# MastersProjectTestBed.net
KiCad netlist of a schematic drawn in EAGLE
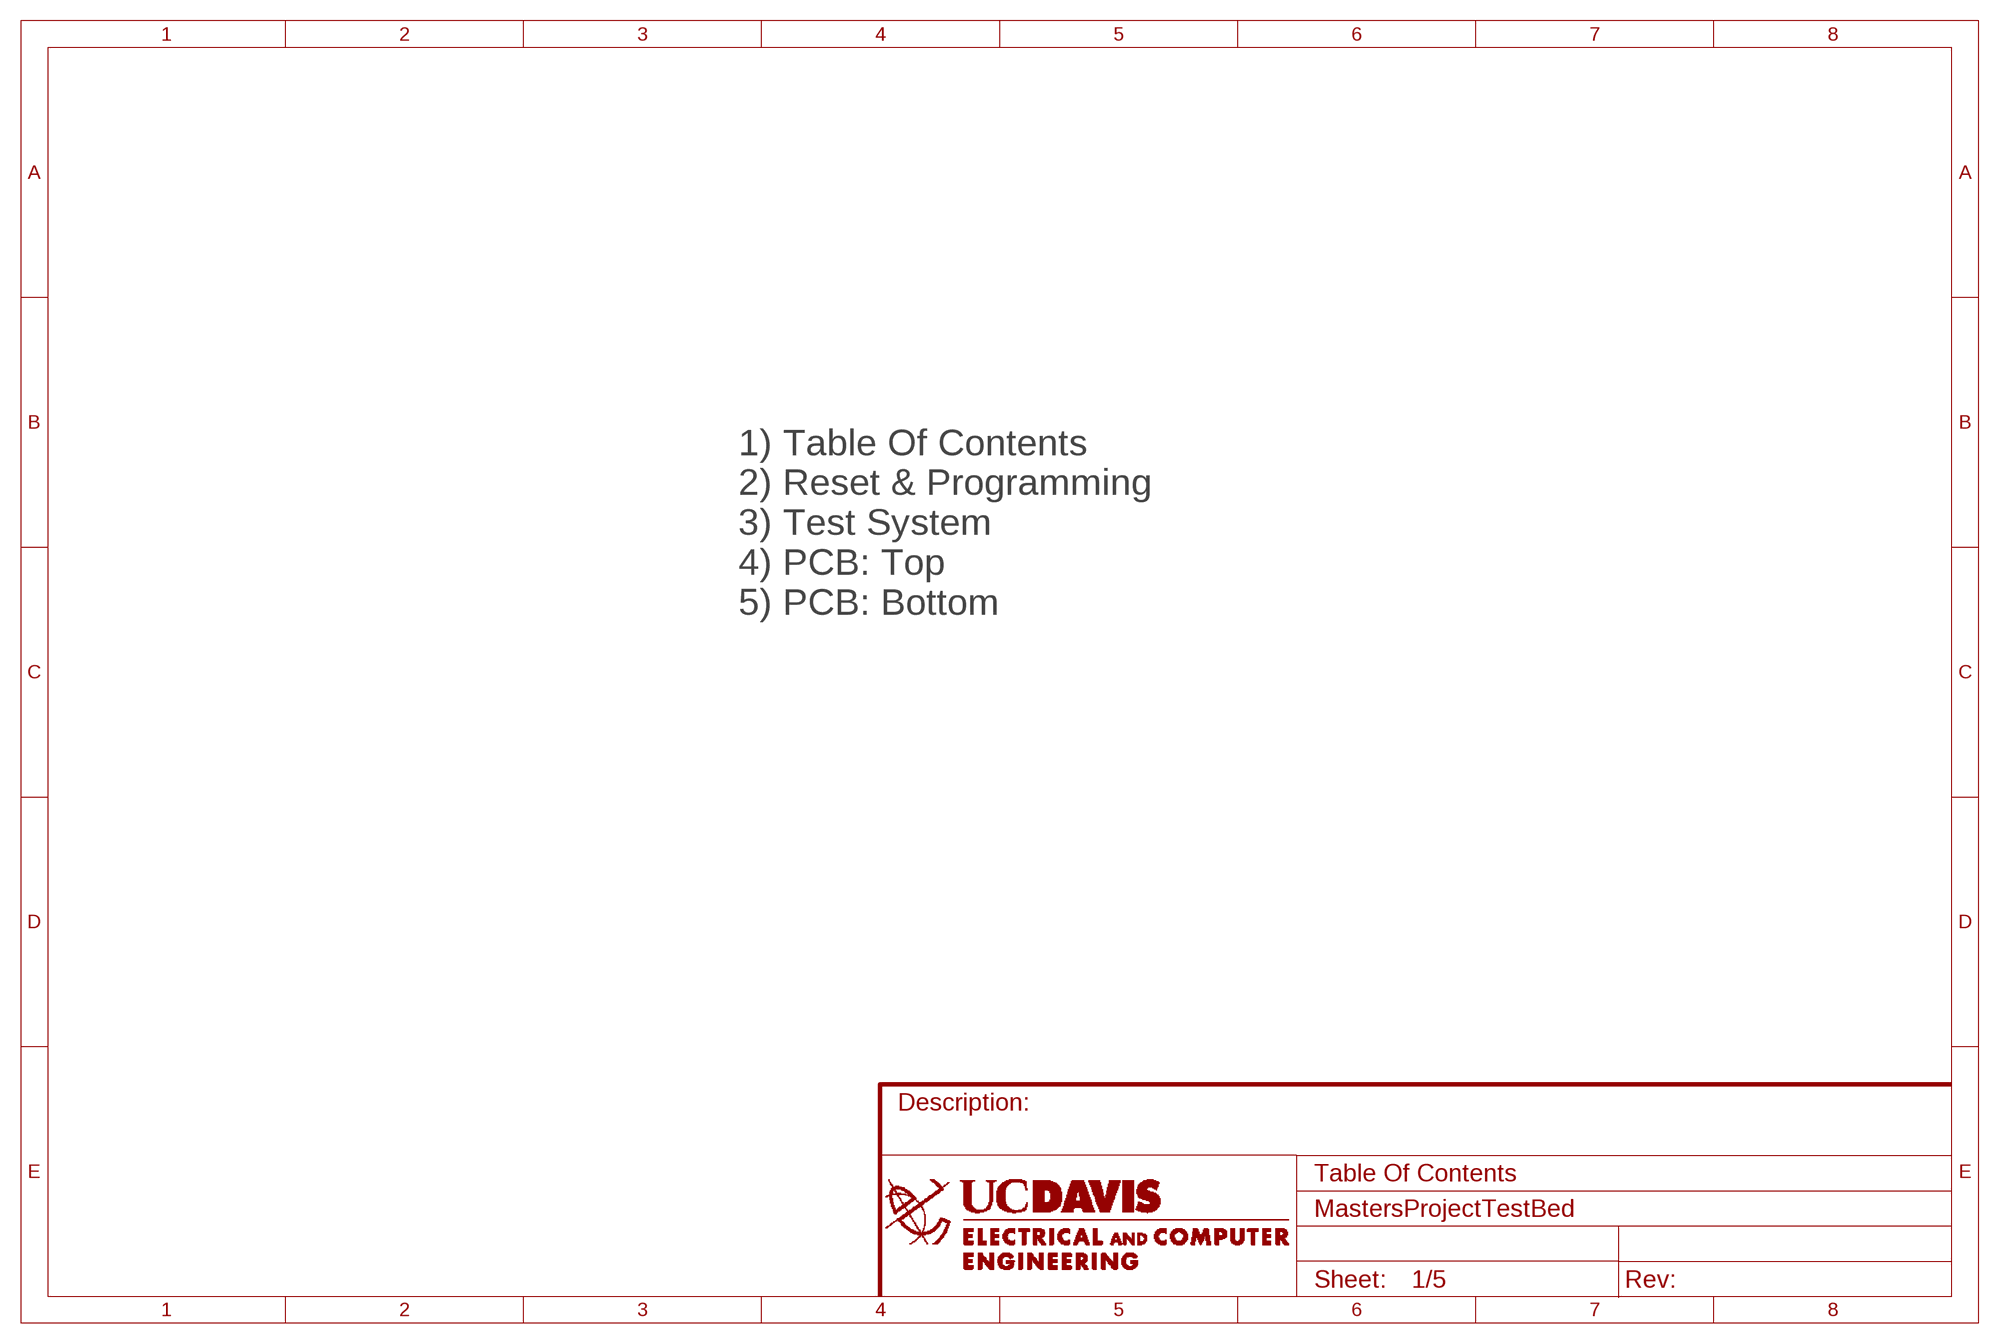
[diagram p0: schematic, sheet 1]
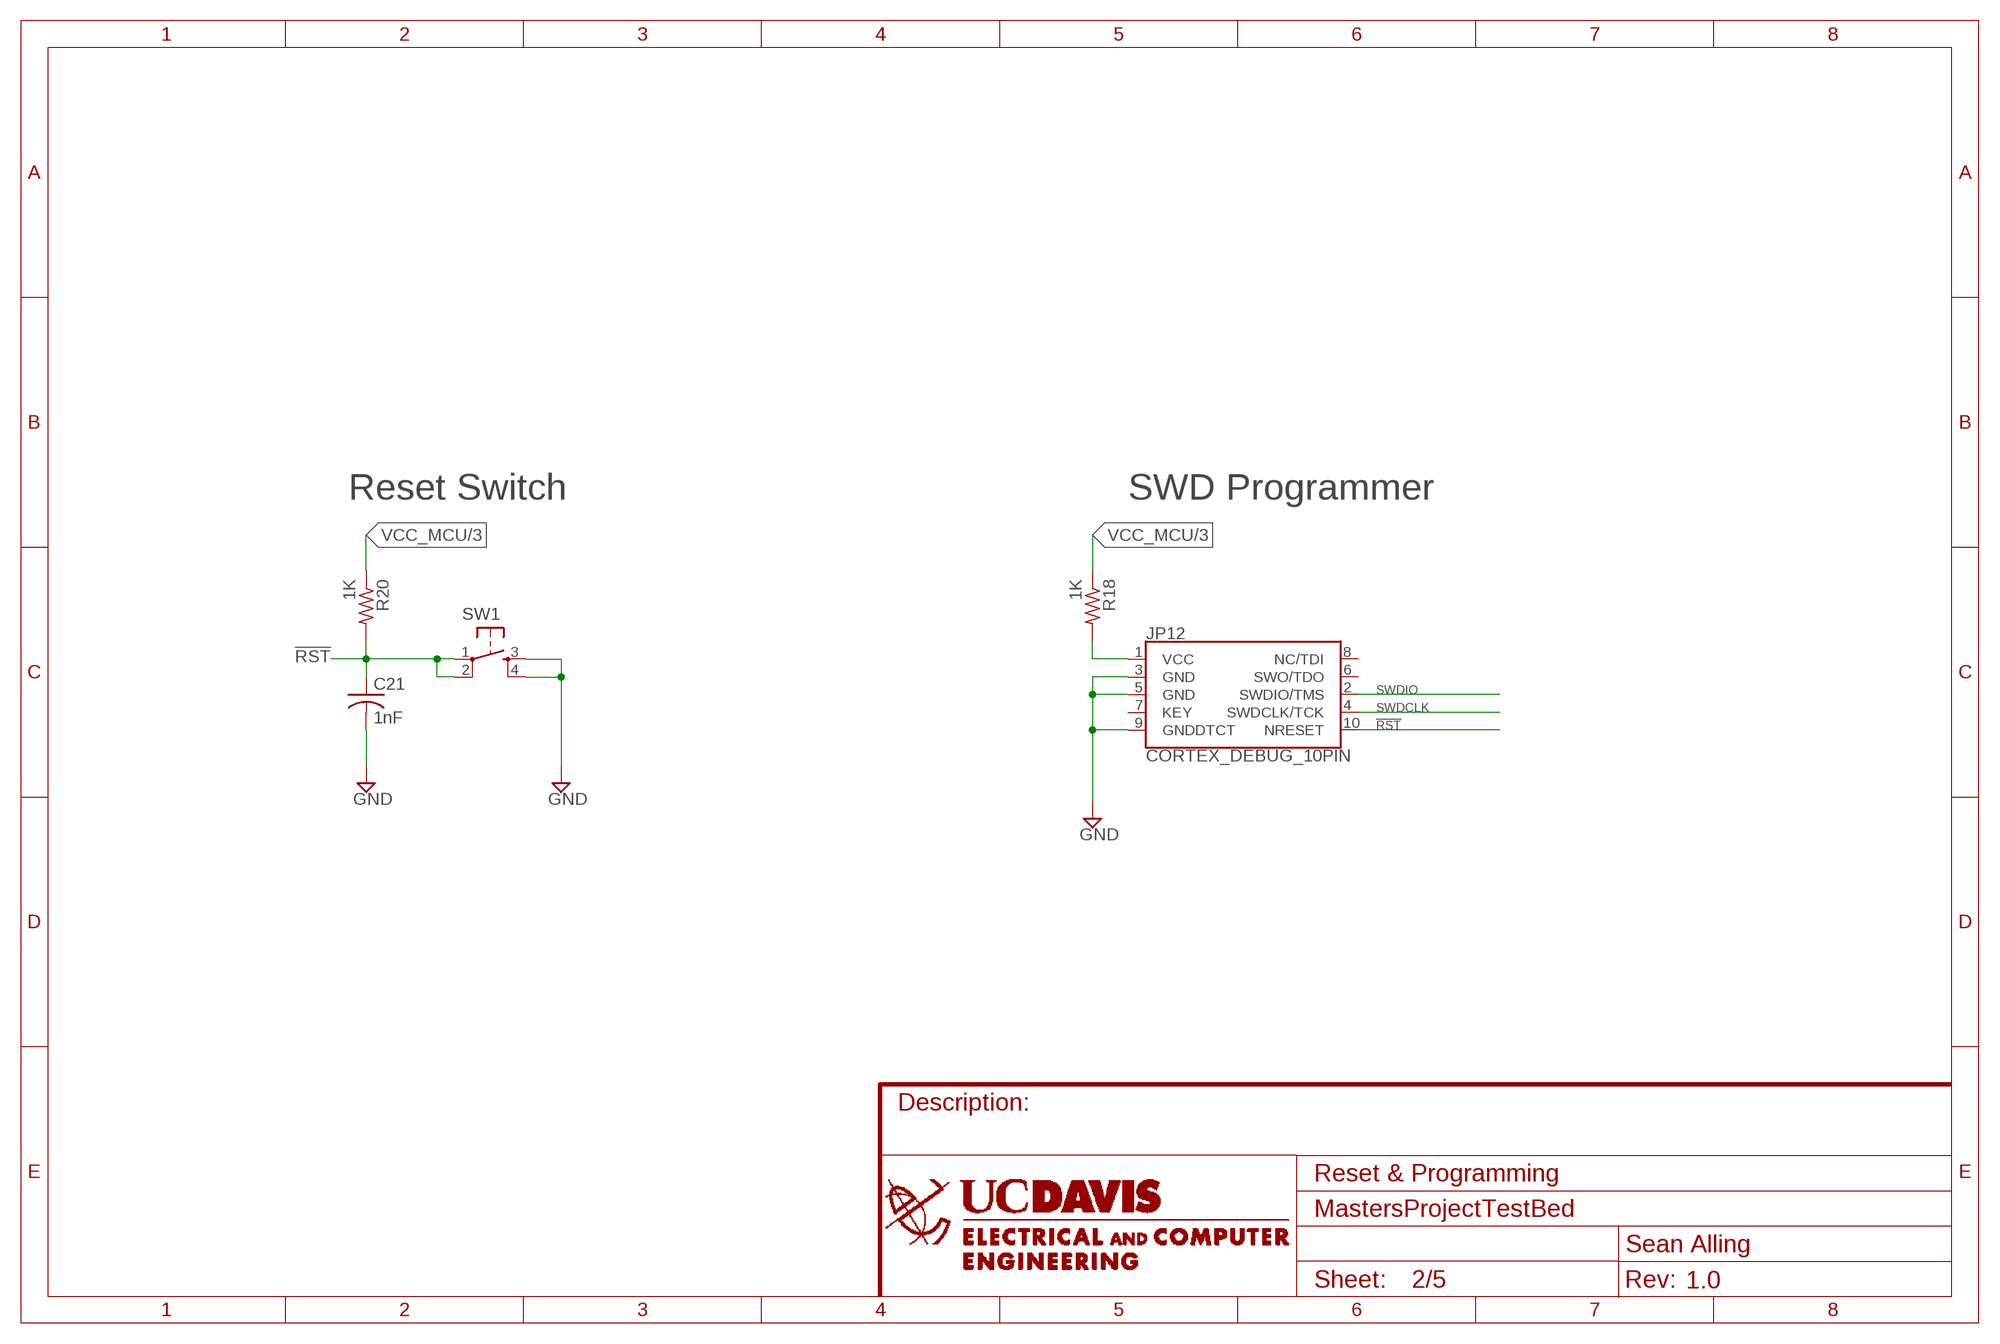
[diagram p1: schematic, sheet 2]
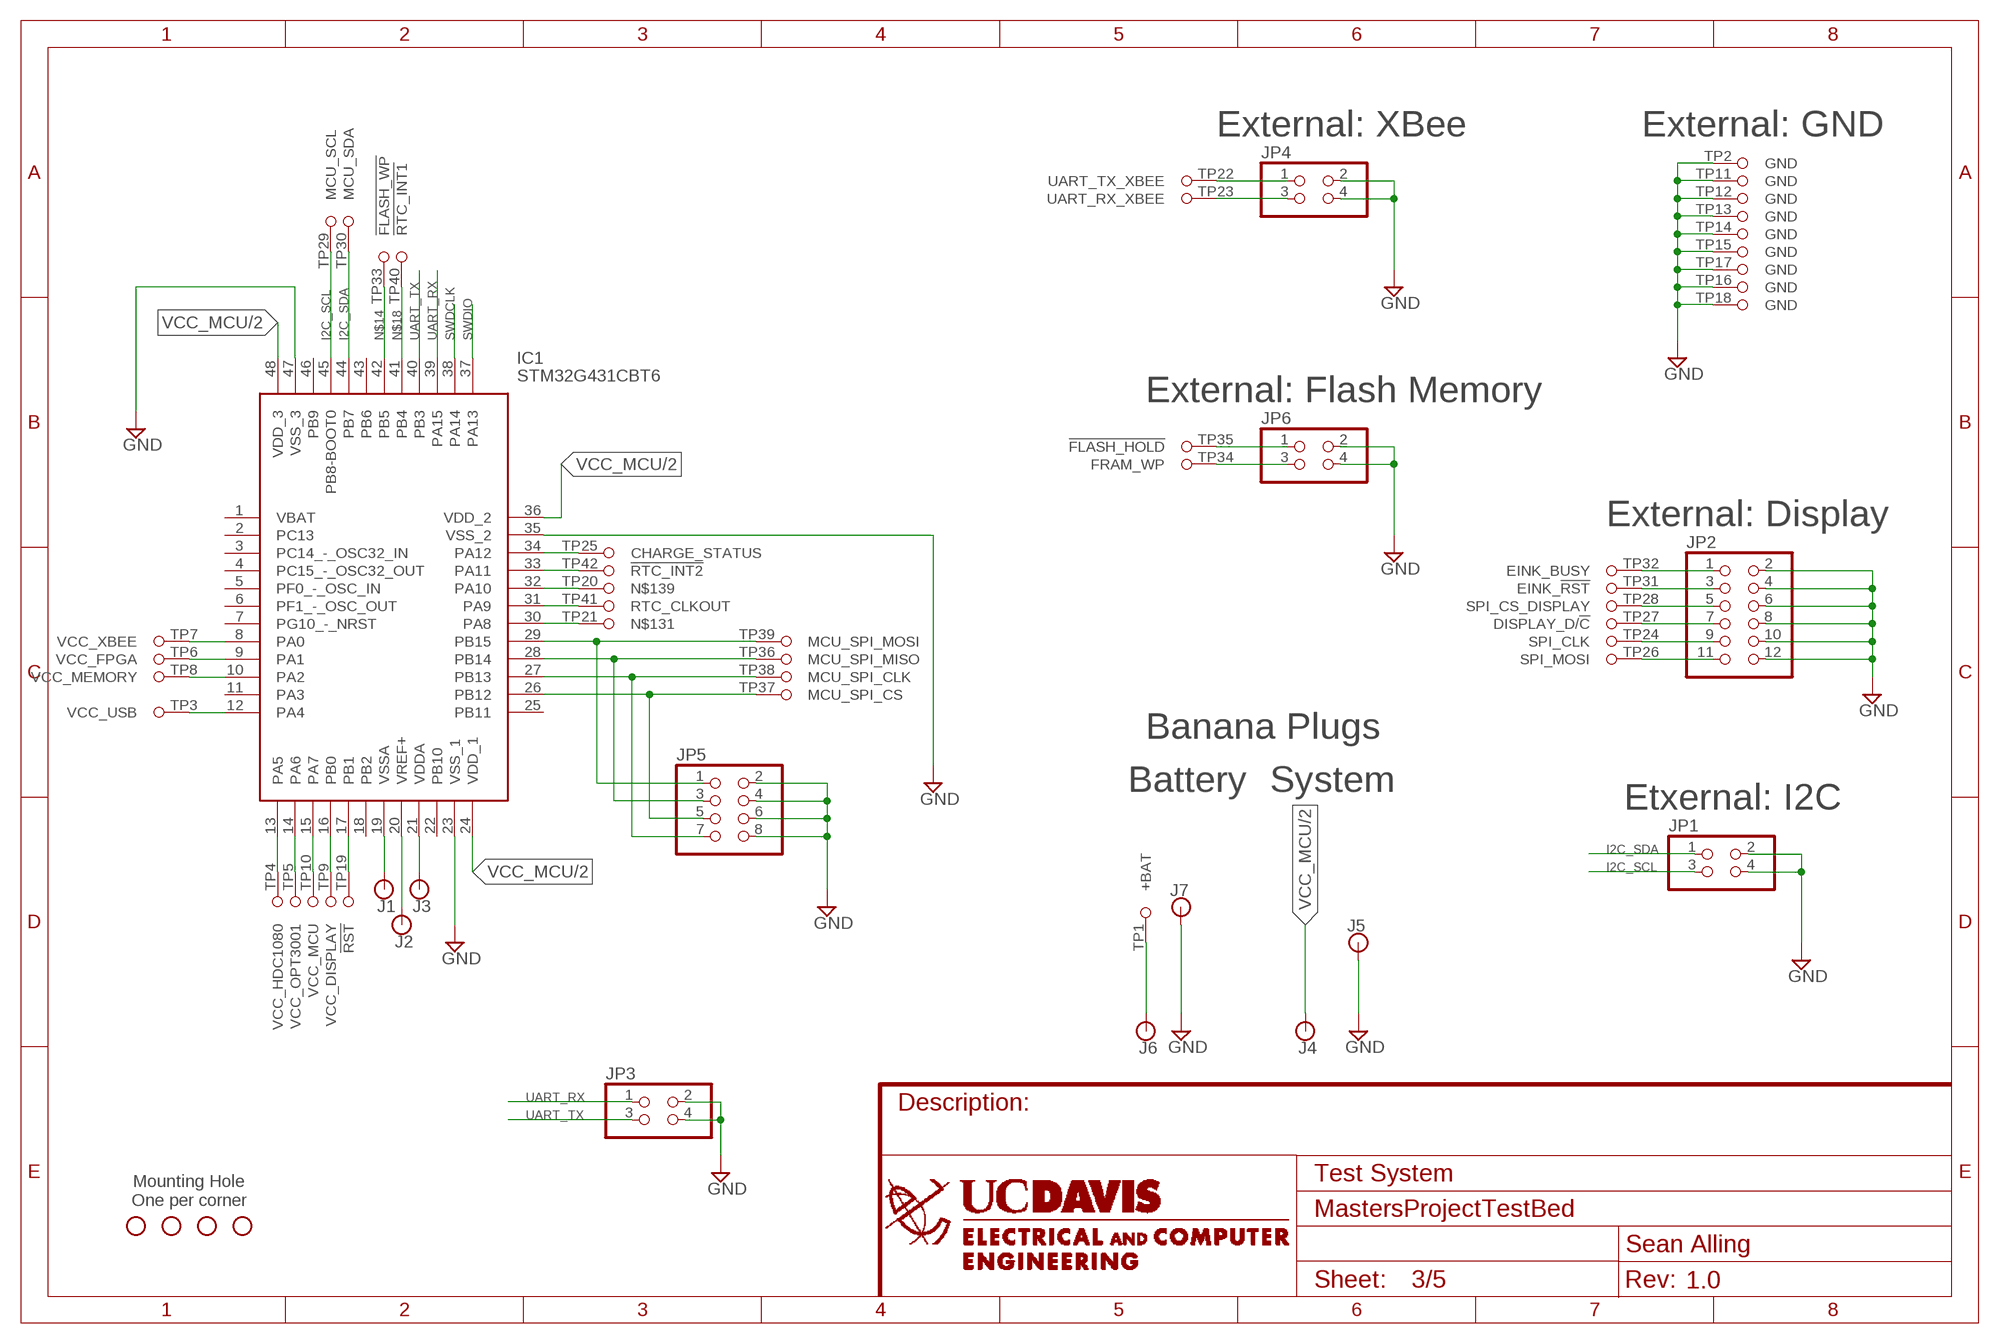
[diagram p2: schematic, sheet 3]
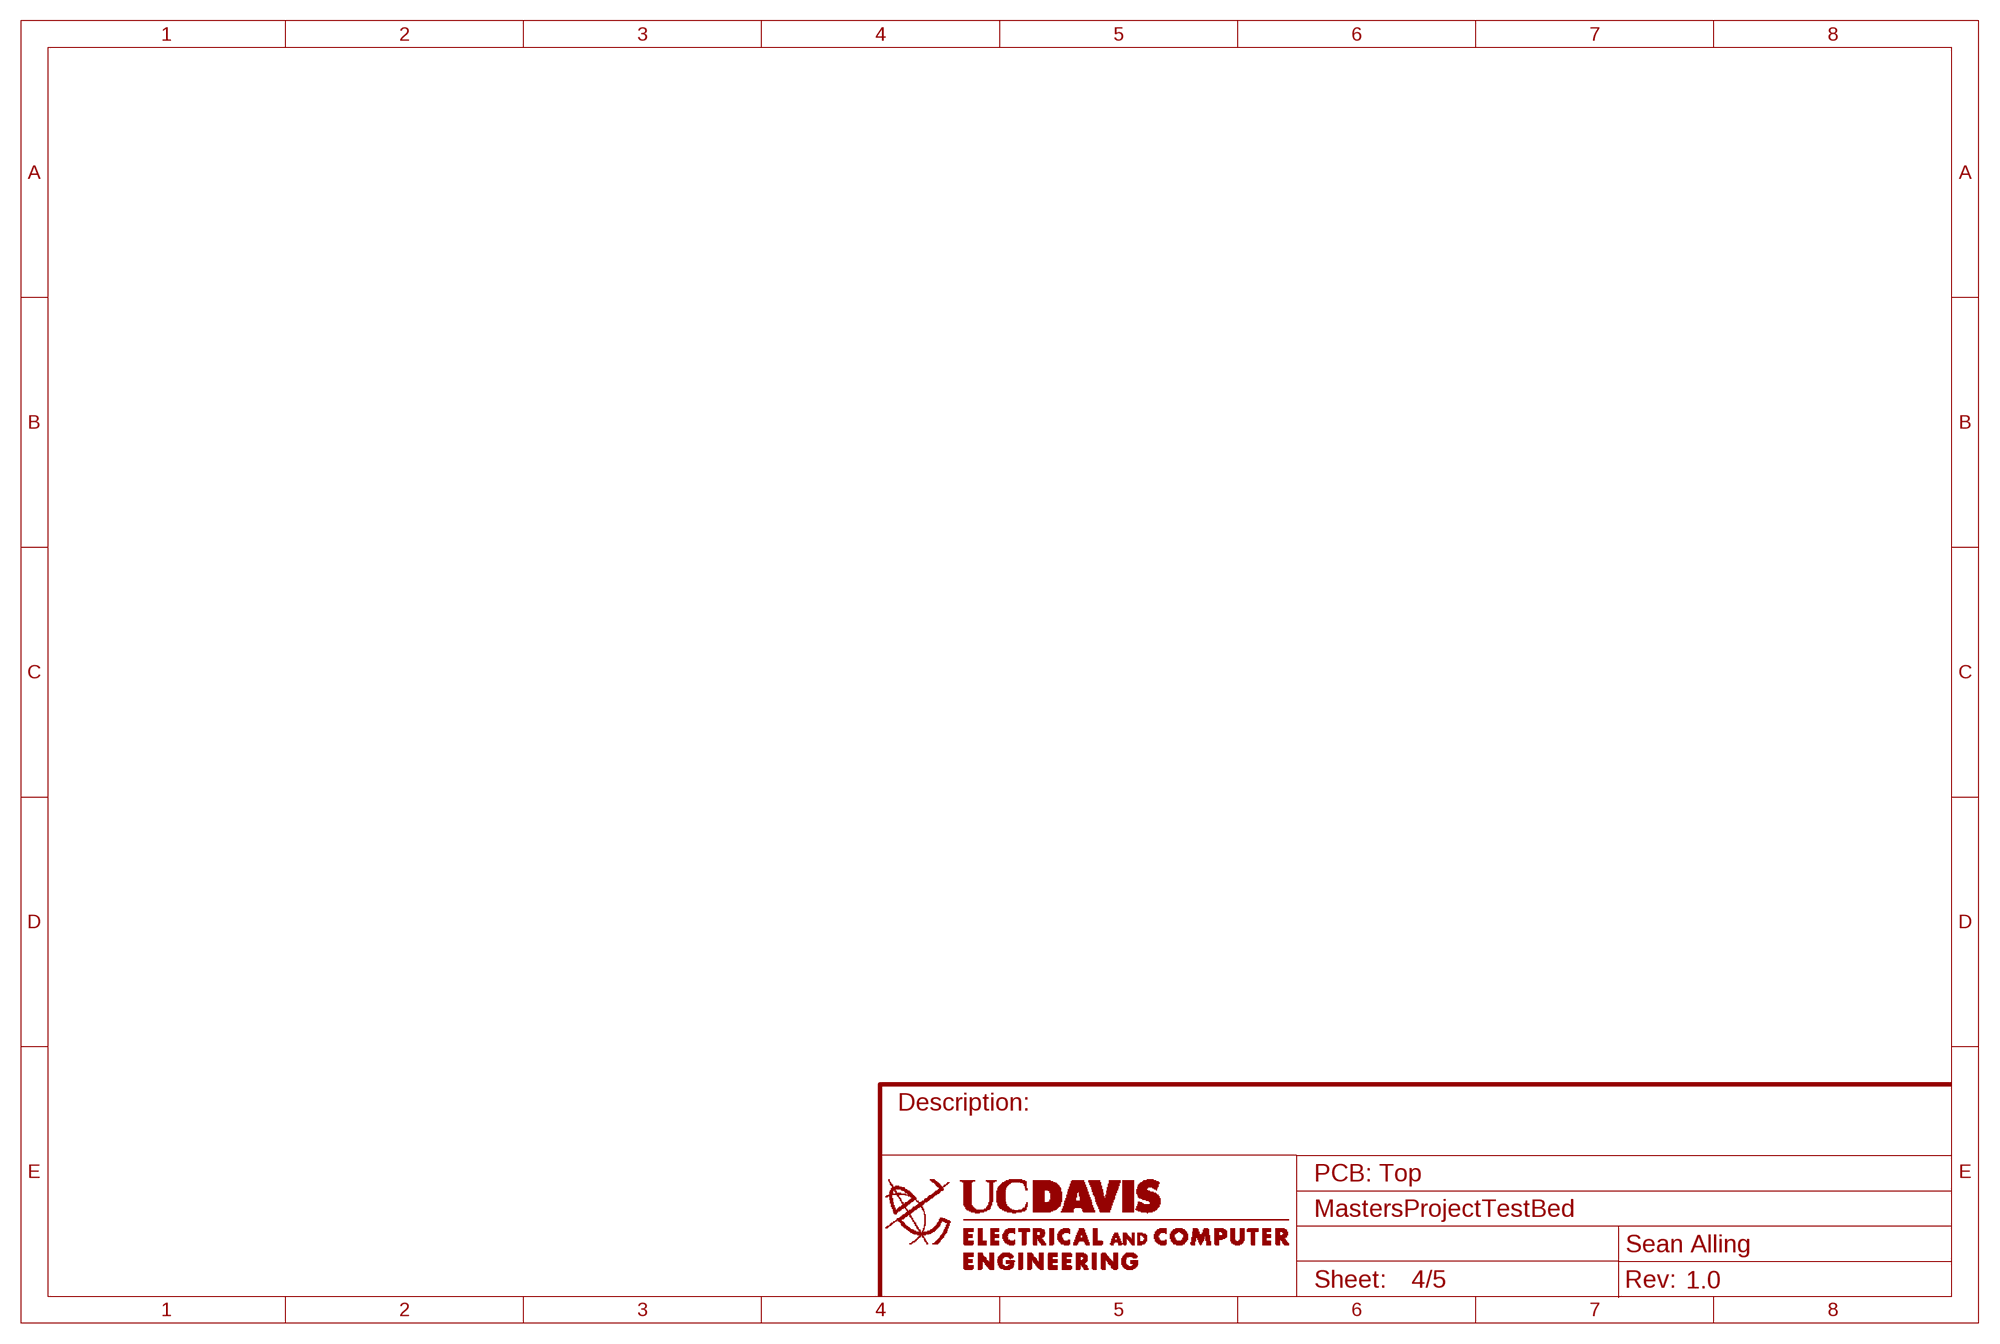
[diagram p3: schematic, sheet 4]
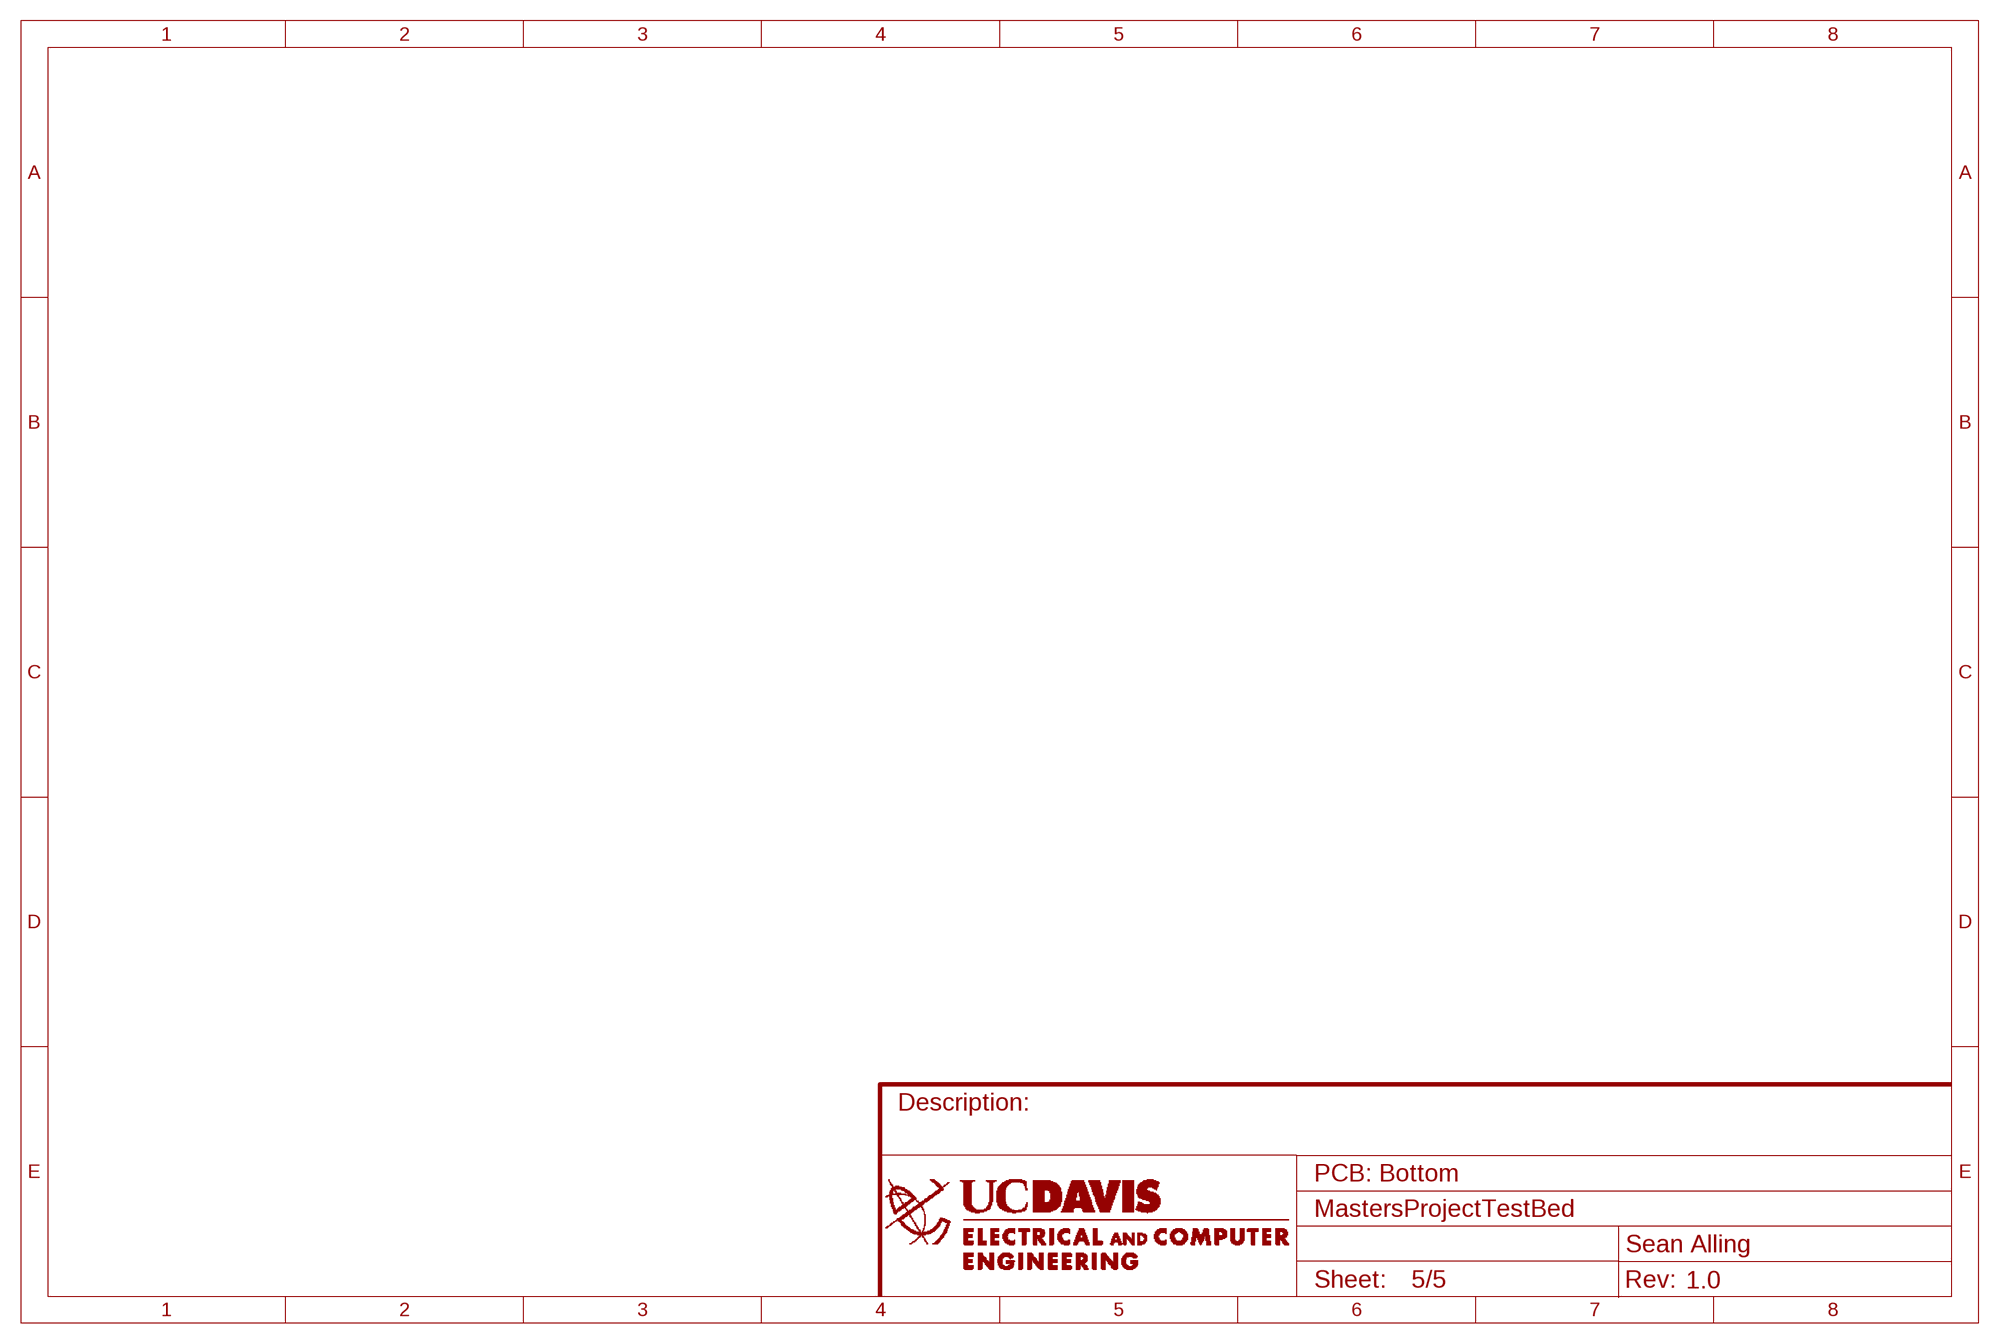
[diagram p4: schematic, sheet 5]

(export (version "E")
  (design (tool "Eeschema 10.0.6"))
  (components
    (comp (ref "H1")
      (value "STAND-OFF")
      (footprint "eagle-import:STAND-OFF")
      (libsource (lib "eagle-import") (part "STAND-OFF"))
    )
    (comp (ref "H2")
      (value "STAND-OFF")
      (footprint "eagle-import:STAND-OFF")
      (libsource (lib "eagle-import") (part "STAND-OFF"))
    )
    (comp (ref "H3")
      (value "STAND-OFF")
      (footprint "eagle-import:STAND-OFF")
      (libsource (lib "eagle-import") (part "STAND-OFF"))
    )
    (comp (ref "H4")
      (value "STAND-OFF")
      (footprint "eagle-import:STAND-OFF")
      (libsource (lib "eagle-import") (part "STAND-OFF"))
    )
    (comp (ref "IC1")
      (value "STM32G431CBT6")
      (footprint "eagle-import:QFP50P900X900X160-48N")
      (fields (field (name "MOUSER_PART_NUMBER") "511-STM32G431CBT6"))
      (libsource (lib "eagle-import") (part "STM32G431CBT6"))
    )
    (comp (ref "J1")
      (value "BANANA_CONN")
      (footprint "eagle-import:BANANA_CONN")
      (libsource (lib "eagle-import") (part "BANANA_CONN"))
    )
    (comp (ref "J2")
      (value "BANANA_CONN")
      (footprint "eagle-import:BANANA_CONN")
      (libsource (lib "eagle-import") (part "BANANA_CONN"))
    )
    (comp (ref "J3")
      (value "BANANA_CONN")
      (footprint "eagle-import:BANANA_CONN")
      (libsource (lib "eagle-import") (part "BANANA_CONN"))
    )
    (comp (ref "J4")
      (value "BANANA_CONN")
      (footprint "eagle-import:BANANA_CONN")
      (libsource (lib "eagle-import") (part "BANANA_CONN"))
    )
    (comp (ref "J5")
      (value "BANANA_CONN")
      (footprint "eagle-import:BANANA_CONN")
      (libsource (lib "eagle-import") (part "BANANA_CONN"))
    )
    (comp (ref "J6")
      (value "BANANA_CONN")
      (footprint "eagle-import:BANANA_CONN")
      (libsource (lib "eagle-import") (part "BANANA_CONN"))
    )
    (comp (ref "J7")
      (value "BANANA_CONN")
      (footprint "eagle-import:BANANA_CONN")
      (libsource (lib "eagle-import") (part "BANANA_CONN"))
    )
    (comp (ref "JP1")
      (value "PINHD-2X2/90")
      (footprint "eagle-import:2X02_90")
      (libsource (lib "eagle-import") (part "PINHD-2X2/90"))
    )
    (comp (ref "JP2")
      (value "PINHD-2X6/90")
      (footprint "eagle-import:2X06_90")
      (libsource (lib "eagle-import") (part "PINHD-2X6/90"))
    )
    (comp (ref "JP3")
      (value "PINHD-2X2/90")
      (footprint "eagle-import:2X02_90")
      (libsource (lib "eagle-import") (part "PINHD-2X2/90"))
    )
    (comp (ref "JP4")
      (value "PINHD-2X2/90")
      (footprint "eagle-import:2X02_90")
      (libsource (lib "eagle-import") (part "PINHD-2X2/90"))
    )
    (comp (ref "JP5")
      (value "PINHD-2X4/90")
      (footprint "eagle-import:2X04_90")
      (libsource (lib "eagle-import") (part "PINHD-2X4/90"))
    )
    (comp (ref "JP6")
      (value "PINHD-2X2/90")
      (footprint "eagle-import:2X02_90")
      (libsource (lib "eagle-import") (part "PINHD-2X2/90"))
    )
    (comp (ref "TP1")
      (value "PCB-POGO")
      (footprint "eagle-import:PCB-POGO")
      (libsource (lib "eagle-import") (part "PCB-POGO"))
    )
    (comp (ref "C21")
      (value "1nF")
      (footprint "eagle-import:C0603")
      (fields (field (name "PARTNO") "08053F102K4T2A"))
      (libsource (lib "eagle-import") (part "C-USC0603"))
    )
    (comp (ref "JP12")
      (value "CORTEX_DEBUG_10PIN")
      (footprint "eagle-import:CORTEX_DEBUG_10PIN")
      (fields (field (name "PARTNO") "3220-10-0100-00"))
      (libsource (lib "eagle-import") (part "CORTEX_DEBUG_10PIN"))
    )
    (comp (ref "R18")
      (value "1K")
      (footprint "eagle-import:R0603")
      (fields (field (name "PARTNO") "RC0805JR-071KL"))
      (libsource (lib "eagle-import") (part "R-US_R0603"))
    )
    (comp (ref "R20")
      (value "1K")
      (footprint "eagle-import:R0603")
      (fields (field (name "PARTNO") "RC0805JR-071KL"))
      (libsource (lib "eagle-import") (part "R-US_R0603"))
    )
    (comp (ref "SW1")
      (value "TACTILE-SWITCH-SMT")
      (footprint "eagle-import:7914G")
      (fields (field (name "PARTNO") "7914G-1-000E"))
      (libsource (lib "eagle-import") (part "TACTILE-SWITCH-SMT"))
    )
  )
  (nets
    (net (code "1") (name "GND") (class "Default")
      (node (ref "C21") (pin "2") (pinfunction "2_2") (pintype "passive"))
      (node (ref "IC1") (pin "23") (pinfunction "VSS_1_23") (pintype "bidirectional"))
      (node (ref "IC1") (pin "35") (pinfunction "VSS_2_35") (pintype "bidirectional"))
      (node (ref "IC1") (pin "47") (pinfunction "VSS_3_47") (pintype "bidirectional"))
      (node (ref "J5") (pin "P$1") (pinfunction "1_P$1") (pintype "passive"))
      (node (ref "J7") (pin "P$1") (pinfunction "1_P$1") (pintype "passive"))
      (node (ref "JP1") (pin "2") (pinfunction "2_2") (pintype "passive"))
      (node (ref "JP1") (pin "4") (pinfunction "4_4") (pintype "passive"))
      (node (ref "JP12") (pin "3") (pinfunction "GND_3") (pintype "bidirectional"))
      (node (ref "JP12") (pin "5") (pinfunction "GND_5") (pintype "bidirectional"))
      (node (ref "JP12") (pin "9") (pinfunction "GNDDTCT_9") (pintype "bidirectional"))
      (node (ref "JP2") (pin "10") (pinfunction "10_10") (pintype "passive"))
      (node (ref "JP2") (pin "12") (pinfunction "12_12") (pintype "passive"))
      (node (ref "JP2") (pin "2") (pinfunction "2_2") (pintype "passive"))
      (node (ref "JP2") (pin "4") (pinfunction "4_4") (pintype "passive"))
      (node (ref "JP2") (pin "6") (pinfunction "6_6") (pintype "passive"))
      (node (ref "JP2") (pin "8") (pinfunction "8_8") (pintype "passive"))
      (node (ref "JP3") (pin "2") (pinfunction "2_2") (pintype "passive"))
      (node (ref "JP3") (pin "4") (pinfunction "4_4") (pintype "passive"))
      (node (ref "JP4") (pin "2") (pinfunction "2_2") (pintype "passive"))
      (node (ref "JP4") (pin "4") (pinfunction "4_4") (pintype "passive"))
      (node (ref "JP5") (pin "2") (pinfunction "2_2") (pintype "passive"))
      (node (ref "JP5") (pin "4") (pinfunction "4_4") (pintype "passive"))
      (node (ref "JP5") (pin "6") (pinfunction "6_6") (pintype "passive"))
      (node (ref "JP5") (pin "8") (pinfunction "8_8") (pintype "passive"))
      (node (ref "JP6") (pin "2") (pinfunction "2_2") (pintype "passive"))
      (node (ref "JP6") (pin "4") (pinfunction "4_4") (pintype "passive"))
      (node (ref "SW1") (pin "3") (pinfunction "3_3") (pintype "passive"))
      (node (ref "SW1") (pin "4") (pinfunction "4_4") (pintype "passive"))
      (node (ref "TP1") (pin "TP11") (pinfunction "GND_TP11") (pintype "bidirectional"))
      (node (ref "TP1") (pin "TP12") (pinfunction "GND_TP12") (pintype "bidirectional"))
      (node (ref "TP1") (pin "TP13") (pinfunction "GND_TP13") (pintype "bidirectional"))
      (node (ref "TP1") (pin "TP14") (pinfunction "GND_TP14") (pintype "bidirectional"))
      (node (ref "TP1") (pin "TP15") (pinfunction "GND_TP15") (pintype "bidirectional"))
      (node (ref "TP1") (pin "TP16") (pinfunction "GND_TP16") (pintype "bidirectional"))
      (node (ref "TP1") (pin "TP17") (pinfunction "GND_TP17") (pintype "bidirectional"))
      (node (ref "TP1") (pin "TP18") (pinfunction "GND_TP18") (pintype "bidirectional"))
      (node (ref "TP1") (pin "TP2") (pinfunction "GND_TP2") (pintype "bidirectional"))
    )
    (net (code "2") (name "I2C_SCL") (class "Default")
      (node (ref "IC1") (pin "45") (pinfunction "PB8-BOOT0_45") (pintype "bidirectional"))
      (node (ref "JP1") (pin "3") (pinfunction "3_3") (pintype "passive"))
      (node (ref "TP1") (pin "TP29") (pinfunction "MCU_SCL_TP29") (pintype "bidirectional"))
    )
    (net (code "3") (name "I2C_SDA") (class "Default")
      (node (ref "IC1") (pin "44") (pinfunction "PB7_44") (pintype "bidirectional"))
      (node (ref "JP1") (pin "1") (pinfunction "1_1") (pintype "passive"))
      (node (ref "TP1") (pin "TP30") (pinfunction "MCU_SDA_TP30") (pintype "bidirectional"))
    )
    (net (code "4") (name "N$14") (class "Default")
      (node (ref "IC1") (pin "42") (pinfunction "PB5_42") (pintype "bidirectional"))
      (node (ref "TP1") (pin "TP33") (pinfunction "~{FLASH_WP}_TP33") (pintype "bidirectional"))
    )
    (net (code "5") (name "N$18") (class "Default")
      (node (ref "IC1") (pin "41") (pinfunction "PB4_41") (pintype "bidirectional"))
      (node (ref "TP1") (pin "TP40") (pinfunction "~{RTC_INT1}_TP40") (pintype "bidirectional"))
    )
    (net (code "6") (name "Net-(IC1-PA0)") (class "Default")
      (node (ref "IC1") (pin "8") (pinfunction "PA0_8") (pintype "bidirectional"))
      (node (ref "TP1") (pin "TP7") (pinfunction "VCC_XBEE_TP7") (pintype "bidirectional"))
    )
    (net (code "7") (name "Net-(IC1-PA1)") (class "Default")
      (node (ref "IC1") (pin "9") (pinfunction "PA1_9") (pintype "bidirectional"))
      (node (ref "TP1") (pin "TP6") (pinfunction "VCC_FPGA_TP6") (pintype "bidirectional"))
    )
    (net (code "8") (name "Net-(IC1-PA2)") (class "Default")
      (node (ref "IC1") (pin "10") (pinfunction "PA2_10") (pintype "bidirectional"))
      (node (ref "TP1") (pin "TP8") (pinfunction "VCC_MEMORY_TP8") (pintype "bidirectional"))
    )
    (net (code "9") (name "Net-(IC1-PA4)") (class "Default")
      (node (ref "IC1") (pin "12") (pinfunction "PA4_12") (pintype "bidirectional"))
      (node (ref "TP1") (pin "TP3") (pinfunction "VCC_USB_TP3") (pintype "bidirectional"))
    )
    (net (code "10") (name "Net-(IC1-PA5)") (class "Default")
      (node (ref "IC1") (pin "13") (pinfunction "PA5_13") (pintype "bidirectional"))
      (node (ref "TP1") (pin "TP4") (pinfunction "VCC_HDC1080_TP4") (pintype "bidirectional"))
    )
    (net (code "11") (name "Net-(IC1-PA6)") (class "Default")
      (node (ref "IC1") (pin "14") (pinfunction "PA6_14") (pintype "bidirectional"))
      (node (ref "TP1") (pin "TP5") (pinfunction "VCC_OPT3001_TP5") (pintype "bidirectional"))
    )
    (net (code "12") (name "Net-(IC1-PA7)") (class "Default")
      (node (ref "IC1") (pin "15") (pinfunction "PA7_15") (pintype "bidirectional"))
      (node (ref "TP1") (pin "TP10") (pinfunction "VCC_MCU_TP10") (pintype "bidirectional"))
    )
    (net (code "13") (name "Net-(IC1-PA8)") (class "Default")
      (node (ref "IC1") (pin "30") (pinfunction "PA8_30") (pintype "bidirectional"))
      (node (ref "TP1") (pin "TP21") (pinfunction "N$131_TP21") (pintype "bidirectional"))
    )
    (net (code "14") (name "Net-(IC1-PA9)") (class "Default")
      (node (ref "IC1") (pin "31") (pinfunction "PA9_31") (pintype "bidirectional"))
      (node (ref "TP1") (pin "TP41") (pinfunction "RTC_CLKOUT_TP41") (pintype "bidirectional"))
    )
    (net (code "15") (name "Net-(IC1-PA10)") (class "Default")
      (node (ref "IC1") (pin "32") (pinfunction "PA10_32") (pintype "bidirectional"))
      (node (ref "TP1") (pin "TP20") (pinfunction "N$139_TP20") (pintype "bidirectional"))
    )
    (net (code "16") (name "Net-(IC1-PA11)") (class "Default")
      (node (ref "IC1") (pin "33") (pinfunction "PA11_33") (pintype "bidirectional"))
      (node (ref "TP1") (pin "TP42") (pinfunction "~{RTC_INT2}_TP42") (pintype "bidirectional"))
    )
    (net (code "17") (name "Net-(IC1-PA12)") (class "Default")
      (node (ref "IC1") (pin "34") (pinfunction "PA12_34") (pintype "bidirectional"))
      (node (ref "TP1") (pin "TP25") (pinfunction "CHARGE_STATUS_TP25") (pintype "bidirectional"))
    )
    (net (code "18") (name "Net-(IC1-PB0)") (class "Default")
      (node (ref "IC1") (pin "16") (pinfunction "PB0_16") (pintype "bidirectional"))
      (node (ref "TP1") (pin "TP9") (pinfunction "VCC_DISPLAY_TP9") (pintype "bidirectional"))
    )
    (net (code "19") (name "Net-(IC1-PB1)") (class "Default")
      (node (ref "IC1") (pin "17") (pinfunction "PB1_17") (pintype "bidirectional"))
      (node (ref "TP1") (pin "TP19") (pinfunction "~{RST}_TP19") (pintype "bidirectional"))
    )
    (net (code "20") (name "Net-(IC1-PB12)") (class "Default")
      (node (ref "IC1") (pin "26") (pinfunction "PB12_26") (pintype "bidirectional"))
      (node (ref "JP5") (pin "5") (pinfunction "5_5") (pintype "passive"))
      (node (ref "TP1") (pin "TP37") (pinfunction "MCU_SPI_CS_TP37") (pintype "bidirectional"))
    )
    (net (code "21") (name "Net-(IC1-PB13)") (class "Default")
      (node (ref "IC1") (pin "27") (pinfunction "PB13_27") (pintype "bidirectional"))
      (node (ref "JP5") (pin "7") (pinfunction "7_7") (pintype "passive"))
      (node (ref "TP1") (pin "TP38") (pinfunction "MCU_SPI_CLK_TP38") (pintype "bidirectional"))
    )
    (net (code "22") (name "Net-(IC1-PB14)") (class "Default")
      (node (ref "IC1") (pin "28") (pinfunction "PB14_28") (pintype "bidirectional"))
      (node (ref "JP5") (pin "3") (pinfunction "3_3") (pintype "passive"))
      (node (ref "TP1") (pin "TP36") (pinfunction "MCU_SPI_MISO_TP36") (pintype "bidirectional"))
    )
    (net (code "23") (name "Net-(IC1-PB15)") (class "Default")
      (node (ref "IC1") (pin "29") (pinfunction "PB15_29") (pintype "bidirectional"))
      (node (ref "JP5") (pin "1") (pinfunction "1_1") (pintype "passive"))
      (node (ref "TP1") (pin "TP39") (pinfunction "MCU_SPI_MOSI_TP39") (pintype "bidirectional"))
    )
    (net (code "24") (name "Net-(IC1-VDDA)") (class "Default")
      (node (ref "IC1") (pin "21") (pinfunction "VDDA_21") (pintype "bidirectional"))
      (node (ref "J3") (pin "P$1") (pinfunction "1_P$1") (pintype "passive"))
    )
    (net (code "25") (name "Net-(IC1-VREF+)") (class "Default")
      (node (ref "IC1") (pin "20") (pinfunction "VREF+_20") (pintype "bidirectional"))
      (node (ref "J2") (pin "P$1") (pinfunction "1_P$1") (pintype "passive"))
    )
    (net (code "26") (name "Net-(IC1-VSSA)") (class "Default")
      (node (ref "IC1") (pin "19") (pinfunction "VSSA_19") (pintype "bidirectional"))
      (node (ref "J1") (pin "P$1") (pinfunction "1_P$1") (pintype "passive"))
    )
    (net (code "27") (name "Net-(J6-1)") (class "Default")
      (node (ref "J6") (pin "P$1") (pinfunction "1_P$1") (pintype "passive"))
      (node (ref "TP1") (pin "TP1") (pinfunction "+BAT_TP1") (pintype "bidirectional"))
    )
    (net (code "28") (name "Net-(JP12-VCC)") (class "Default")
      (node (ref "JP12") (pin "1") (pinfunction "VCC_1") (pintype "bidirectional"))
      (node (ref "R18") (pin "2") (pinfunction "2_2") (pintype "passive"))
    )
    (net (code "29") (name "Net-(TP1A-~{FLASH_HOLD})") (class "Default")
      (node (ref "JP6") (pin "1") (pinfunction "1_1") (pintype "passive"))
      (node (ref "TP1") (pin "TP35") (pinfunction "~{FLASH_HOLD}_TP35") (pintype "bidirectional"))
    )
    (net (code "30") (name "Net-(TP1AD-SPI_CLK)") (class "Default")
      (node (ref "JP2") (pin "9") (pinfunction "9_9") (pintype "passive"))
      (node (ref "TP1") (pin "TP24") (pinfunction "SPI_CLK_TP24") (pintype "bidirectional"))
    )
    (net (code "31") (name "Net-(TP1AE-SPI_CS_DISPLAY)") (class "Default")
      (node (ref "JP2") (pin "5") (pinfunction "5_5") (pintype "passive"))
      (node (ref "TP1") (pin "TP28") (pinfunction "SPI_CS_DISPLAY_TP28") (pintype "bidirectional"))
    )
    (net (code "32") (name "Net-(TP1AF-SPI_MOSI)") (class "Default")
      (node (ref "JP2") (pin "11") (pinfunction "11_11") (pintype "passive"))
      (node (ref "TP1") (pin "TP26") (pinfunction "SPI_MOSI_TP26") (pintype "bidirectional"))
    )
    (net (code "33") (name "Net-(TP1AG-UART_RX_XBEE)") (class "Default")
      (node (ref "JP4") (pin "3") (pinfunction "3_3") (pintype "passive"))
      (node (ref "TP1") (pin "TP23") (pinfunction "UART_RX_XBEE_TP23") (pintype "bidirectional"))
    )
    (net (code "34") (name "Net-(TP1AH-UART_TX_XBEE)") (class "Default")
      (node (ref "JP4") (pin "1") (pinfunction "1_1") (pintype "passive"))
      (node (ref "TP1") (pin "TP22") (pinfunction "UART_TX_XBEE_TP22") (pintype "bidirectional"))
    )
    (net (code "35") (name "Net-(TP1H-DISPLAY_D{slash}~{C})") (class "Default")
      (node (ref "JP2") (pin "7") (pinfunction "7_7") (pintype "passive"))
      (node (ref "TP1") (pin "TP27") (pinfunction "DISPLAY_D/~{C}_TP27") (pintype "bidirectional"))
    )
    (net (code "36") (name "Net-(TP1I-EINK_~{RST})") (class "Default")
      (node (ref "JP2") (pin "3") (pinfunction "3_3") (pintype "passive"))
      (node (ref "TP1") (pin "TP31") (pinfunction "EINK_~{RST}_TP31") (pintype "bidirectional"))
    )
    (net (code "37") (name "Net-(TP1J-EINK_BUSY)") (class "Default")
      (node (ref "JP2") (pin "1") (pinfunction "1_1") (pintype "passive"))
      (node (ref "TP1") (pin "TP32") (pinfunction "EINK_BUSY_TP32") (pintype "bidirectional"))
    )
    (net (code "38") (name "Net-(TP1K-FRAM_WP)") (class "Default")
      (node (ref "JP6") (pin "3") (pinfunction "3_3") (pintype "passive"))
      (node (ref "TP1") (pin "TP34") (pinfunction "FRAM_WP_TP34") (pintype "bidirectional"))
    )
    (net (code "39") (name "SWDCLK") (class "Default")
      (node (ref "IC1") (pin "38") (pinfunction "PA14_38") (pintype "bidirectional"))
      (node (ref "JP12") (pin "4") (pinfunction "SWDCLK/TCK_4") (pintype "bidirectional"))
    )
    (net (code "40") (name "SWDIO") (class "Default")
      (node (ref "IC1") (pin "37") (pinfunction "PA13_37") (pintype "bidirectional"))
      (node (ref "JP12") (pin "2") (pinfunction "SWDIO/TMS_2") (pintype "bidirectional"))
    )
    (net (code "41") (name "UART_RX") (class "Default")
      (node (ref "IC1") (pin "39") (pinfunction "PA15_39") (pintype "bidirectional"))
      (node (ref "JP3") (pin "1") (pinfunction "1_1") (pintype "passive"))
    )
    (net (code "42") (name "UART_TX") (class "Default")
      (node (ref "IC1") (pin "40") (pinfunction "PB3_40") (pintype "bidirectional"))
      (node (ref "JP3") (pin "3") (pinfunction "3_3") (pintype "passive"))
    )
    (net (code "43") (name "VCC_MCU") (class "Default")
      (node (ref "IC1") (pin "24") (pinfunction "VDD_1_24") (pintype "bidirectional"))
      (node (ref "IC1") (pin "36") (pinfunction "VDD_2_36") (pintype "bidirectional"))
      (node (ref "IC1") (pin "48") (pinfunction "VDD_3_48") (pintype "bidirectional"))
      (node (ref "J4") (pin "P$1") (pinfunction "1_P$1") (pintype "passive"))
      (node (ref "R18") (pin "1") (pinfunction "1_1") (pintype "passive"))
      (node (ref "R20") (pin "1") (pinfunction "1_1") (pintype "passive"))
    )
    (net (code "44") (name "unconnected-(IC1-PA3-Pad11)") (class "Default")
      (node (ref "IC1") (pin "11") (pinfunction "PA3_11") (pintype "bidirectional"))
    )
    (net (code "45") (name "unconnected-(IC1-PB2-Pad18)") (class "Default")
      (node (ref "IC1") (pin "18") (pinfunction "PB2_18") (pintype "bidirectional"))
    )
    (net (code "46") (name "unconnected-(IC1-PB6-Pad43)") (class "Default")
      (node (ref "IC1") (pin "43") (pinfunction "PB6_43") (pintype "bidirectional"))
    )
    (net (code "47") (name "unconnected-(IC1-PB9-Pad46)") (class "Default")
      (node (ref "IC1") (pin "46") (pinfunction "PB9_46") (pintype "bidirectional"))
    )
    (net (code "48") (name "unconnected-(IC1-PB10-Pad22)") (class "Default")
      (node (ref "IC1") (pin "22") (pinfunction "PB10_22") (pintype "bidirectional"))
    )
    (net (code "49") (name "unconnected-(IC1-PB11-Pad25)") (class "Default")
      (node (ref "IC1") (pin "25") (pinfunction "PB11_25") (pintype "bidirectional"))
    )
    (net (code "50") (name "unconnected-(IC1-PC13-Pad2)") (class "Default")
      (node (ref "IC1") (pin "2") (pinfunction "PC13_2") (pintype "bidirectional"))
    )
    (net (code "51") (name "unconnected-(IC1-PC14_-_OSC32_IN-Pad3)") (class "Default")
      (node (ref "IC1") (pin "3") (pinfunction "PC14_-_OSC32_IN_3") (pintype "bidirectional"))
    )
    (net (code "52") (name "unconnected-(IC1-PC15_-_OSC32_OUT-Pad4)") (class "Default")
      (node (ref "IC1") (pin "4") (pinfunction "PC15_-_OSC32_OUT_4") (pintype "bidirectional"))
    )
    (net (code "53") (name "unconnected-(IC1-PF0_-_OSC_IN-Pad5)") (class "Default")
      (node (ref "IC1") (pin "5") (pinfunction "PF0_-_OSC_IN_5") (pintype "bidirectional"))
    )
    (net (code "54") (name "unconnected-(IC1-PF1_-_OSC_OUT-Pad6)") (class "Default")
      (node (ref "IC1") (pin "6") (pinfunction "PF1_-_OSC_OUT_6") (pintype "bidirectional"))
    )
    (net (code "55") (name "unconnected-(IC1-PG10_-_NRST-Pad7)") (class "Default")
      (node (ref "IC1") (pin "7") (pinfunction "PG10_-_NRST_7") (pintype "bidirectional"))
    )
    (net (code "56") (name "unconnected-(IC1-VBAT-Pad1)") (class "Default")
      (node (ref "IC1") (pin "1") (pinfunction "VBAT_1") (pintype "bidirectional"))
    )
    (net (code "57") (name "unconnected-(JP12-KEY-Pad7)") (class "Default")
      (node (ref "JP12") (pin "7") (pinfunction "KEY_7") (pintype "bidirectional"))
    )
    (net (code "58") (name "unconnected-(JP12-NC{slash}TDI-Pad8)") (class "Default")
      (node (ref "JP12") (pin "8") (pinfunction "NC/TDI_8") (pintype "bidirectional"))
    )
    (net (code "59") (name "unconnected-(JP12-SWO{slash}TDO-Pad6)") (class "Default")
      (node (ref "JP12") (pin "6") (pinfunction "SWO/TDO_6") (pintype "bidirectional"))
    )
    (net (code "60") (name "~{RST}") (class "Default")
      (node (ref "C21") (pin "1") (pinfunction "1_1") (pintype "passive"))
      (node (ref "JP12") (pin "10") (pinfunction "NRESET_10") (pintype "bidirectional"))
      (node (ref "R20") (pin "2") (pinfunction "2_2") (pintype "passive"))
      (node (ref "SW1") (pin "1") (pinfunction "1_1") (pintype "passive"))
      (node (ref "SW1") (pin "2") (pinfunction "2_2") (pintype "passive"))
    )
  )
)
